# PMSM_500W_Controller_Driver.net
KiCad netlist of a schematic drawn in Altium Designer
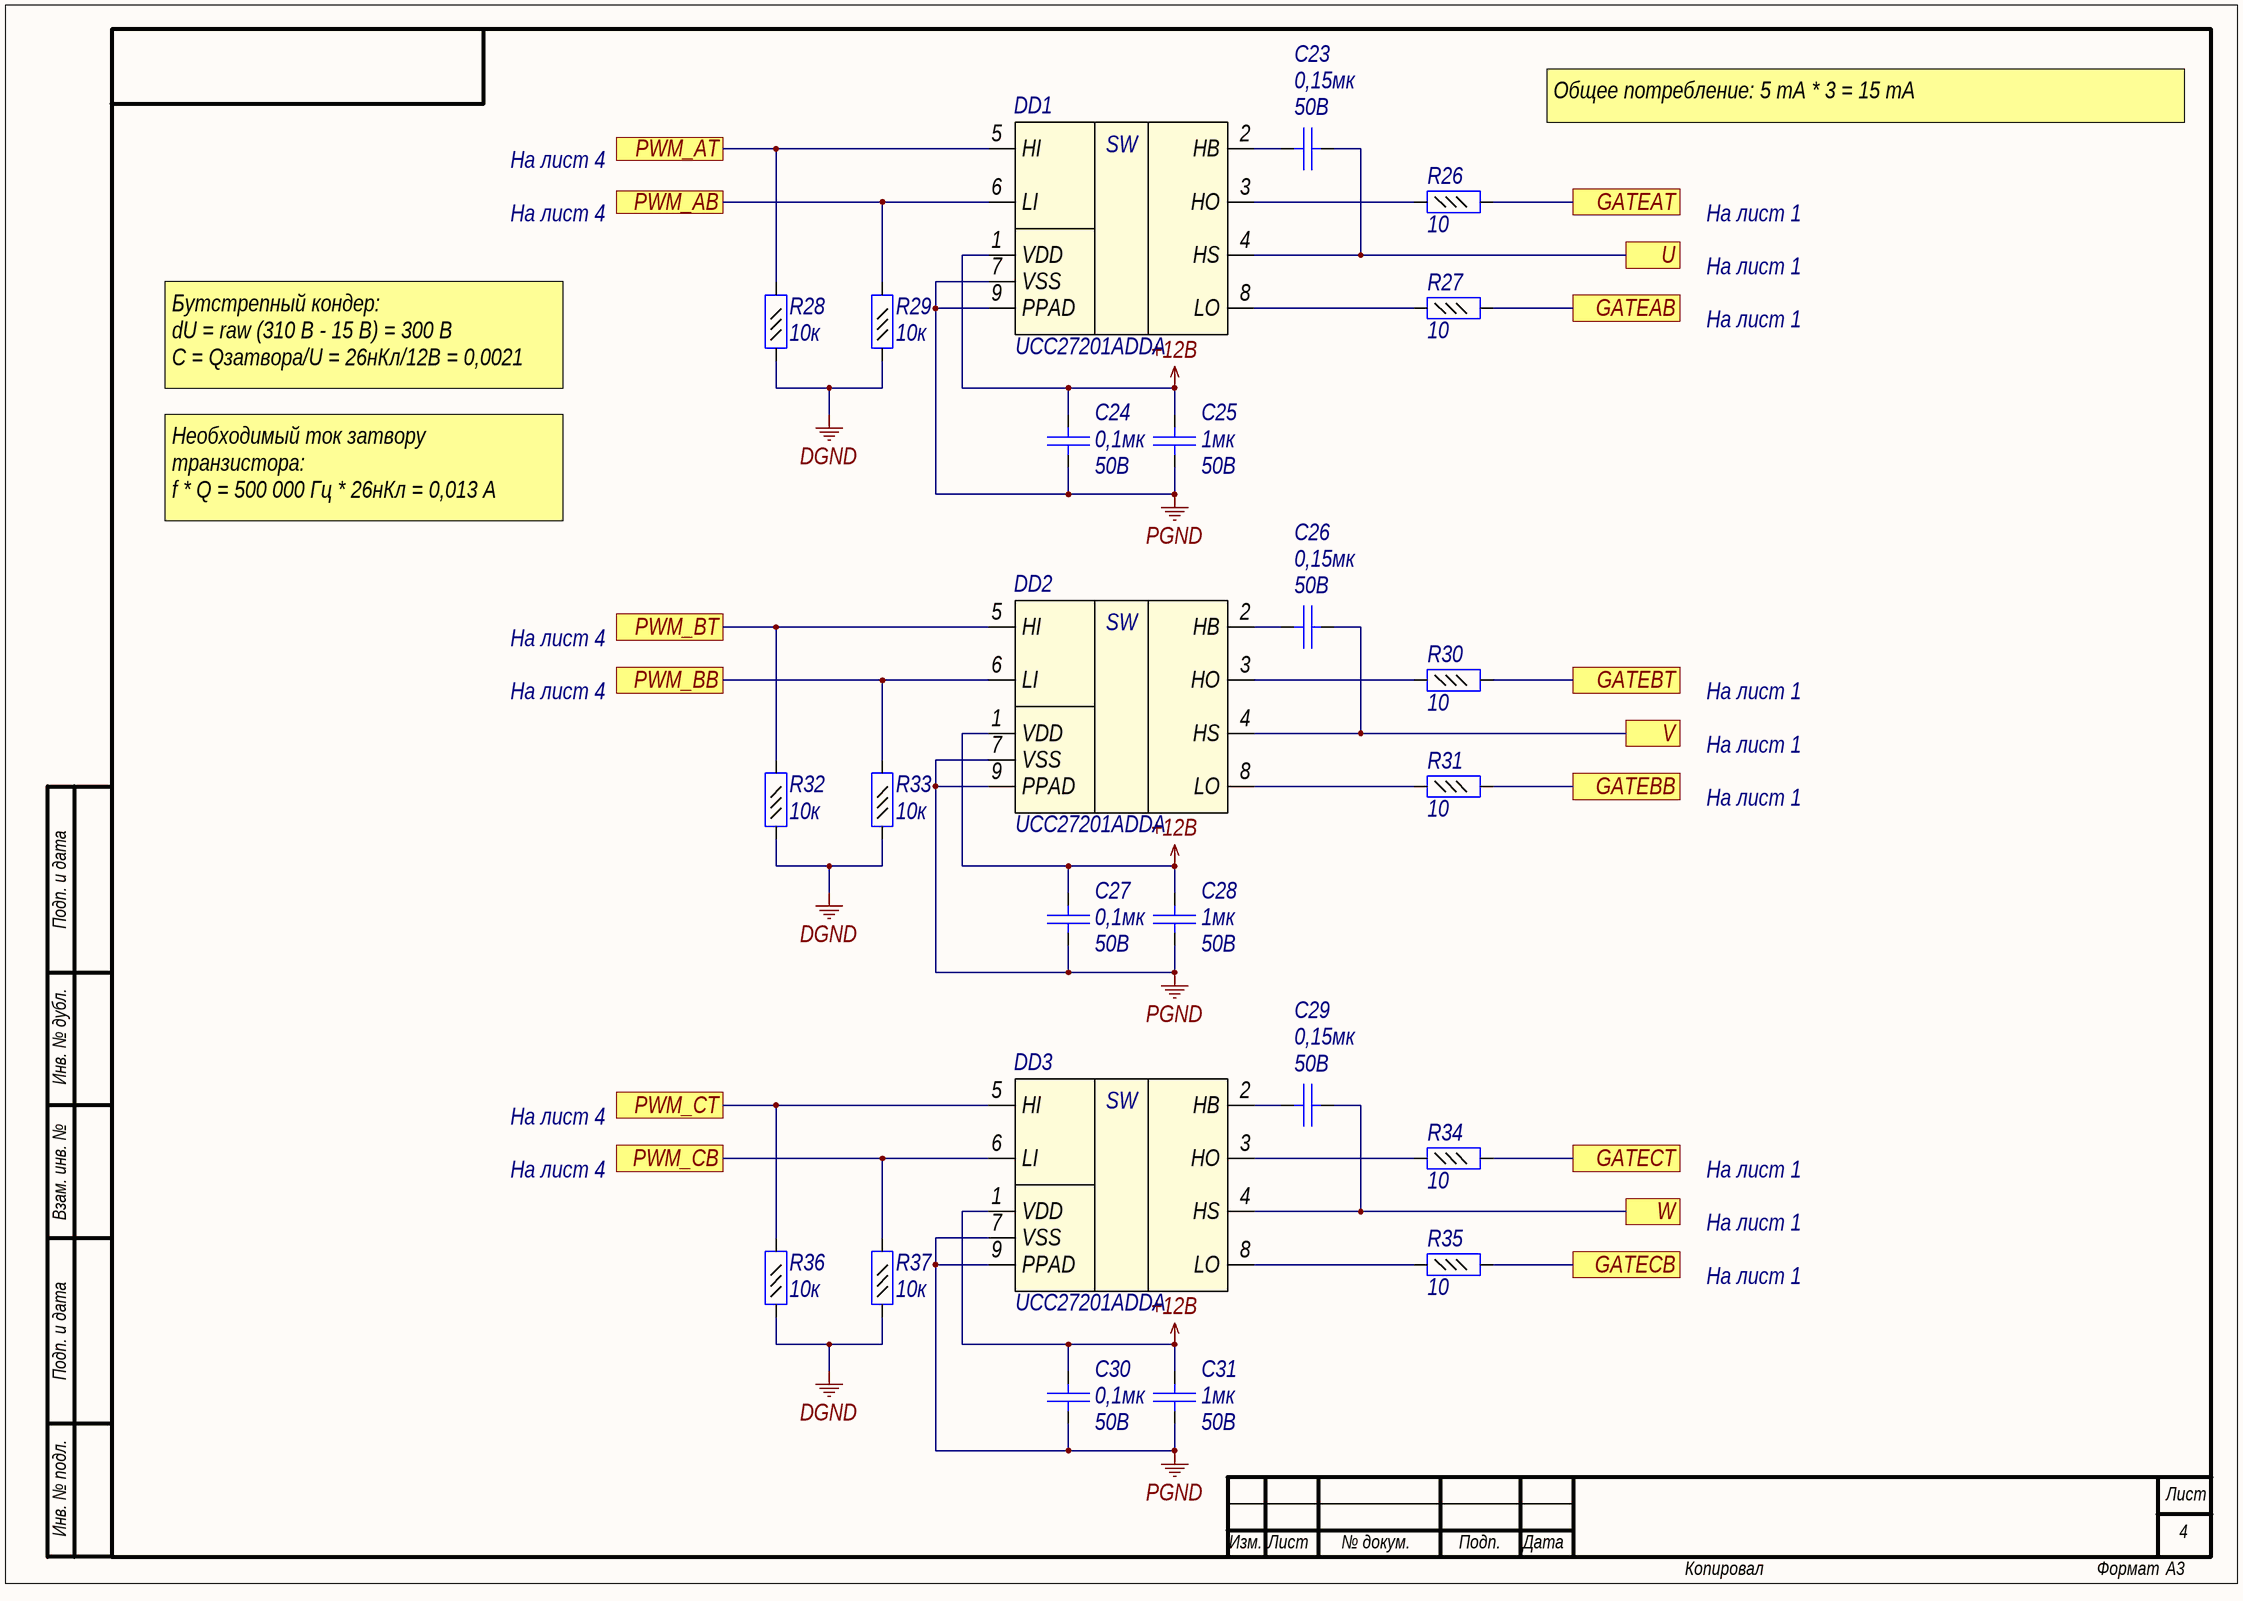
[diagram p0: PMSM_500W_Controller_Driver.SchDoc]

(export (version "E")
  (design (tool "Eeschema 10.0.6"))
  (components
    (comp (ref "C23")
      (value "0,15мк")
      (footprint "C1812")
      (description "Конденсатор")
      (fields (field (name "VOLTAGE") "50В") (field (name "PART NUMBER") "C4532C0G1H154J250KA"))
      (libsource (lib "MOP44") (part "Capacitor"))
    )
    (comp (ref "C24")
      (value "0,1мк")
      (footprint "C0402")
      (description "Конденсатор")
      (fields
        (field (name "VOLTAGE") "50В")
        (field (name "PART NUMBER") "GRM155R71H104KE14D")
        (field (name "Comment") "Capacitor")
      )
      (libsource (lib "MOP44") (part "Capacitor"))
    )
    (comp (ref "C25")
      (value "1мк")
      (footprint "C0805")
      (description "Конденсатор")
      (fields
        (field (name "VOLTAGE") "50B")
        (field (name "PART NUMBER") "GRM21BR71H105K")
        (field (name "Comment") "Capacitor")
      )
      (libsource (lib "MOP44") (part "Capacitor"))
    )
    (comp (ref "C26")
      (value "0,15мк")
      (footprint "C1812")
      (description "Конденсатор")
      (fields (field (name "VOLTAGE") "50В") (field (name "PART NUMBER") "C4532C0G1H154J250KA"))
      (libsource (lib "MOP44") (part "Capacitor"))
    )
    (comp (ref "C27")
      (value "0,1мк")
      (footprint "C0402")
      (description "Конденсатор")
      (fields
        (field (name "VOLTAGE") "50В")
        (field (name "PART NUMBER") "GRM155R71H104KE14D")
        (field (name "Comment") "Capacitor")
      )
      (libsource (lib "MOP44") (part "Capacitor"))
    )
    (comp (ref "C28")
      (value "1мк")
      (footprint "C0805")
      (description "Конденсатор")
      (fields
        (field (name "VOLTAGE") "50B")
        (field (name "PART NUMBER") "GRM21BR71H105K")
        (field (name "Comment") "Capacitor")
      )
      (libsource (lib "MOP44") (part "Capacitor"))
    )
    (comp (ref "C29")
      (value "0,15мк")
      (footprint "C1812")
      (description "Конденсатор")
      (fields (field (name "VOLTAGE") "50В") (field (name "PART NUMBER") "C4532C0G1H154J250KA"))
      (libsource (lib "MOP44") (part "Capacitor"))
    )
    (comp (ref "C30")
      (value "0,1мк")
      (footprint "C0402")
      (description "Конденсатор")
      (fields
        (field (name "VOLTAGE") "50В")
        (field (name "PART NUMBER") "GRM155R71H104KE14D")
        (field (name "Comment") "Capacitor")
      )
      (libsource (lib "MOP44") (part "Capacitor"))
    )
    (comp (ref "C31")
      (value "1мк")
      (footprint "C0805")
      (description "Конденсатор")
      (fields
        (field (name "VOLTAGE") "50B")
        (field (name "PART NUMBER") "GRM21BR71H105K")
        (field (name "Comment") "Capacitor")
      )
      (libsource (lib "MOP44") (part "Capacitor"))
    )
    (comp (ref "DD1")
      (value "UCC27201A")
      (footprint "SO8 POWERPAD")
      (description "120-V Boot, 3-A Peak, High-Frequency, High-Side and Low-Side Driver")
      (fields (field (name "PART NUMBER") "UCC27201ADDA"))
      (libsource (lib "MOP44") (part "UCC27201A"))
    )
    (comp (ref "DD2")
      (value "UCC27201A")
      (footprint "SO8 POWERPAD")
      (description "120-V Boot, 3-A Peak, High-Frequency, High-Side and Low-Side Driver")
      (fields (field (name "PART NUMBER") "UCC27201ADDA"))
      (libsource (lib "MOP44") (part "UCC27201A"))
    )
    (comp (ref "DD3")
      (value "UCC27201A")
      (footprint "SO8 POWERPAD")
      (description "120-V Boot, 3-A Peak, High-Frequency, High-Side and Low-Side Driver")
      (fields (field (name "PART NUMBER") "UCC27201ADDA"))
      (libsource (lib "MOP44") (part "UCC27201A"))
    )
    (comp (ref "R26")
      (value "10")
      (footprint "R0402")
      (description "Резистор")
      (fields (field (name "PART NUMBER") "RC0402FR-0710RL") (field (name "POWER") "0,062Вт"))
      (libsource (lib "") (part "Resistor_0,062Вт_1"))
    )
    (comp (ref "R27")
      (value "10")
      (footprint "R0402")
      (description "Резистор")
      (fields (field (name "PART NUMBER") "RC0402FR-0710RL") (field (name "POWER") "0,062Вт"))
      (libsource (lib "") (part "Resistor_0,062Вт_1"))
    )
    (comp (ref "R28")
      (value "10к")
      (footprint "R0402")
      (description "Резистор")
      (fields (field (name "PART NUMBER") "RC0402FR-0710KL") (field (name "POWER") "0,062Вт"))
      (libsource (lib "MOP44") (part "Resistor_0,062Вт"))
    )
    (comp (ref "R29")
      (value "10к")
      (footprint "R0402")
      (description "Резистор")
      (fields (field (name "PART NUMBER") "RC0402FR-0710KL") (field (name "POWER") "0,062Вт"))
      (libsource (lib "MOP44") (part "Resistor_0,062Вт"))
    )
    (comp (ref "R30")
      (value "10")
      (footprint "R0402")
      (description "Резистор")
      (fields (field (name "PART NUMBER") "RC0402FR-0710RL") (field (name "POWER") "0,062Вт"))
      (libsource (lib "") (part "Resistor_0,062Вт_1"))
    )
    (comp (ref "R31")
      (value "10")
      (footprint "R0402")
      (description "Резистор")
      (fields (field (name "PART NUMBER") "RC0402FR-0710RL") (field (name "POWER") "0,062Вт"))
      (libsource (lib "") (part "Resistor_0,062Вт_1"))
    )
    (comp (ref "R32")
      (value "10к")
      (footprint "R0402")
      (description "Резистор")
      (fields (field (name "PART NUMBER") "RC0402FR-0710KL") (field (name "POWER") "0,062Вт"))
      (libsource (lib "MOP44") (part "Resistor_0,062Вт"))
    )
    (comp (ref "R33")
      (value "10к")
      (footprint "R0402")
      (description "Резистор")
      (fields (field (name "PART NUMBER") "RC0402FR-0710KL") (field (name "POWER") "0,062Вт"))
      (libsource (lib "MOP44") (part "Resistor_0,062Вт"))
    )
    (comp (ref "R34")
      (value "10")
      (footprint "R0402")
      (description "Резистор")
      (fields (field (name "PART NUMBER") "RC0402FR-0710RL") (field (name "POWER") "0,062Вт"))
      (libsource (lib "") (part "Resistor_0,062Вт_1"))
    )
    (comp (ref "R35")
      (value "10")
      (footprint "R0402")
      (description "Резистор")
      (fields (field (name "PART NUMBER") "RC0402FR-0710RL") (field (name "POWER") "0,062Вт"))
      (libsource (lib "") (part "Resistor_0,062Вт_1"))
    )
    (comp (ref "R36")
      (value "10к")
      (footprint "R0402")
      (description "Резистор")
      (fields (field (name "PART NUMBER") "RC0402FR-0710KL") (field (name "POWER") "0,062Вт"))
      (libsource (lib "MOP44") (part "Resistor_0,062Вт"))
    )
    (comp (ref "R37")
      (value "10к")
      (footprint "R0402")
      (description "Резистор")
      (fields (field (name "PART NUMBER") "RC0402FR-0710KL") (field (name "POWER") "0,062Вт"))
      (libsource (lib "MOP44") (part "Resistor_0,062Вт"))
    )
  )
  (nets
    (net (code "1") (name "+12B") (class "Default")
      (node (ref "C24") (pin "2") (pinfunction "2_2") (pintype "passive"))
      (node (ref "C25") (pin "2") (pinfunction "2_2") (pintype "passive"))
      (node (ref "C27") (pin "2") (pinfunction "2_2") (pintype "passive"))
      (node (ref "C28") (pin "2") (pinfunction "2_2") (pintype "passive"))
      (node (ref "C30") (pin "2") (pinfunction "2_2") (pintype "passive"))
      (node (ref "C31") (pin "2") (pinfunction "2_2") (pintype "passive"))
      (node (ref "DD1") (pin "1") (pinfunction "VDD_1") (pintype "passive"))
      (node (ref "DD2") (pin "1") (pinfunction "VDD_1") (pintype "passive"))
      (node (ref "DD3") (pin "1") (pinfunction "VDD_1") (pintype "passive"))
    )
    (net (code "2") (name "/GATEAB") (class "Default")
      (node (ref "R27") (pin "2") (pinfunction "2_2") (pintype "passive"))
    )
    (net (code "3") (name "/GATEAT") (class "Default")
      (node (ref "R26") (pin "2") (pinfunction "2_2") (pintype "passive"))
    )
    (net (code "4") (name "/GATEBB") (class "Default")
      (node (ref "R31") (pin "2") (pinfunction "2_2") (pintype "passive"))
    )
    (net (code "5") (name "/GATEBT") (class "Default")
      (node (ref "R30") (pin "2") (pinfunction "2_2") (pintype "passive"))
    )
    (net (code "6") (name "/GATECB") (class "Default")
      (node (ref "R35") (pin "2") (pinfunction "2_2") (pintype "passive"))
    )
    (net (code "7") (name "/GATECT") (class "Default")
      (node (ref "R34") (pin "2") (pinfunction "2_2") (pintype "passive"))
    )
    (net (code "8") (name "/PWM_AB") (class "Default")
      (node (ref "DD1") (pin "6") (pinfunction "LI_6") (pintype "passive"))
      (node (ref "R29") (pin "2") (pinfunction "2_2") (pintype "passive"))
    )
    (net (code "9") (name "/PWM_AT") (class "Default")
      (node (ref "DD1") (pin "5") (pinfunction "HI_5") (pintype "passive"))
      (node (ref "R28") (pin "2") (pinfunction "2_2") (pintype "passive"))
    )
    (net (code "10") (name "/PWM_BB") (class "Default")
      (node (ref "DD2") (pin "6") (pinfunction "LI_6") (pintype "passive"))
      (node (ref "R33") (pin "2") (pinfunction "2_2") (pintype "passive"))
    )
    (net (code "11") (name "/PWM_BT") (class "Default")
      (node (ref "DD2") (pin "5") (pinfunction "HI_5") (pintype "passive"))
      (node (ref "R32") (pin "2") (pinfunction "2_2") (pintype "passive"))
    )
    (net (code "12") (name "/PWM_CB") (class "Default")
      (node (ref "DD3") (pin "6") (pinfunction "LI_6") (pintype "passive"))
      (node (ref "R37") (pin "2") (pinfunction "2_2") (pintype "passive"))
    )
    (net (code "13") (name "/PWM_CT") (class "Default")
      (node (ref "DD3") (pin "5") (pinfunction "HI_5") (pintype "passive"))
      (node (ref "R36") (pin "2") (pinfunction "2_2") (pintype "passive"))
    )
    (net (code "14") (name "/U") (class "Default")
      (node (ref "C23") (pin "2") (pinfunction "2_2") (pintype "passive"))
      (node (ref "DD1") (pin "4") (pinfunction "HS_4") (pintype "passive"))
    )
    (net (code "15") (name "/V") (class "Default")
      (node (ref "C26") (pin "2") (pinfunction "2_2") (pintype "passive"))
      (node (ref "DD2") (pin "4") (pinfunction "HS_4") (pintype "passive"))
    )
    (net (code "16") (name "/W") (class "Default")
      (node (ref "C29") (pin "2") (pinfunction "2_2") (pintype "passive"))
      (node (ref "DD3") (pin "4") (pinfunction "HS_4") (pintype "passive"))
    )
    (net (code "17") (name "DGND") (class "Default")
      (node (ref "R28") (pin "1") (pinfunction "1_1") (pintype "passive"))
      (node (ref "R29") (pin "1") (pinfunction "1_1") (pintype "passive"))
      (node (ref "R32") (pin "1") (pinfunction "1_1") (pintype "passive"))
      (node (ref "R33") (pin "1") (pinfunction "1_1") (pintype "passive"))
      (node (ref "R36") (pin "1") (pinfunction "1_1") (pintype "passive"))
      (node (ref "R37") (pin "1") (pinfunction "1_1") (pintype "passive"))
    )
    (net (code "18") (name "Net-(DD1-HB)") (class "Default")
      (node (ref "C23") (pin "1") (pinfunction "1_1") (pintype "passive"))
      (node (ref "DD1") (pin "2") (pinfunction "HB_2") (pintype "passive"))
    )
    (net (code "19") (name "Net-(DD1-HO)") (class "Default")
      (node (ref "DD1") (pin "3") (pinfunction "HO_3") (pintype "passive"))
      (node (ref "R26") (pin "1") (pinfunction "1_1") (pintype "passive"))
    )
    (net (code "20") (name "Net-(DD1-LO)") (class "Default")
      (node (ref "DD1") (pin "8") (pinfunction "LO_8") (pintype "passive"))
      (node (ref "R27") (pin "1") (pinfunction "1_1") (pintype "passive"))
    )
    (net (code "21") (name "Net-(DD2-HB)") (class "Default")
      (node (ref "C26") (pin "1") (pinfunction "1_1") (pintype "passive"))
      (node (ref "DD2") (pin "2") (pinfunction "HB_2") (pintype "passive"))
    )
    (net (code "22") (name "Net-(DD2-HO)") (class "Default")
      (node (ref "DD2") (pin "3") (pinfunction "HO_3") (pintype "passive"))
      (node (ref "R30") (pin "1") (pinfunction "1_1") (pintype "passive"))
    )
    (net (code "23") (name "Net-(DD2-LO)") (class "Default")
      (node (ref "DD2") (pin "8") (pinfunction "LO_8") (pintype "passive"))
      (node (ref "R31") (pin "1") (pinfunction "1_1") (pintype "passive"))
    )
    (net (code "24") (name "Net-(DD3-HB)") (class "Default")
      (node (ref "C29") (pin "1") (pinfunction "1_1") (pintype "passive"))
      (node (ref "DD3") (pin "2") (pinfunction "HB_2") (pintype "passive"))
    )
    (net (code "25") (name "Net-(DD3-HO)") (class "Default")
      (node (ref "DD3") (pin "3") (pinfunction "HO_3") (pintype "passive"))
      (node (ref "R34") (pin "1") (pinfunction "1_1") (pintype "passive"))
    )
    (net (code "26") (name "Net-(DD3-LO)") (class "Default")
      (node (ref "DD3") (pin "8") (pinfunction "LO_8") (pintype "passive"))
      (node (ref "R35") (pin "1") (pinfunction "1_1") (pintype "passive"))
    )
    (net (code "27") (name "PGND") (class "Default")
      (node (ref "C24") (pin "1") (pinfunction "1_1") (pintype "passive"))
      (node (ref "C25") (pin "1") (pinfunction "1_1") (pintype "passive"))
      (node (ref "C27") (pin "1") (pinfunction "1_1") (pintype "passive"))
      (node (ref "C28") (pin "1") (pinfunction "1_1") (pintype "passive"))
      (node (ref "C30") (pin "1") (pinfunction "1_1") (pintype "passive"))
      (node (ref "C31") (pin "1") (pinfunction "1_1") (pintype "passive"))
      (node (ref "DD1") (pin "7") (pinfunction "VSS_7") (pintype "passive"))
      (node (ref "DD1") (pin "9") (pinfunction "PPAD_9") (pintype "passive"))
      (node (ref "DD2") (pin "7") (pinfunction "VSS_7") (pintype "passive"))
      (node (ref "DD2") (pin "9") (pinfunction "PPAD_9") (pintype "passive"))
      (node (ref "DD3") (pin "7") (pinfunction "VSS_7") (pintype "passive"))
      (node (ref "DD3") (pin "9") (pinfunction "PPAD_9") (pintype "passive"))
    )
  )
)
